# ExpanderBottom.net
KiCad netlist of a schematic drawn in EAGLE
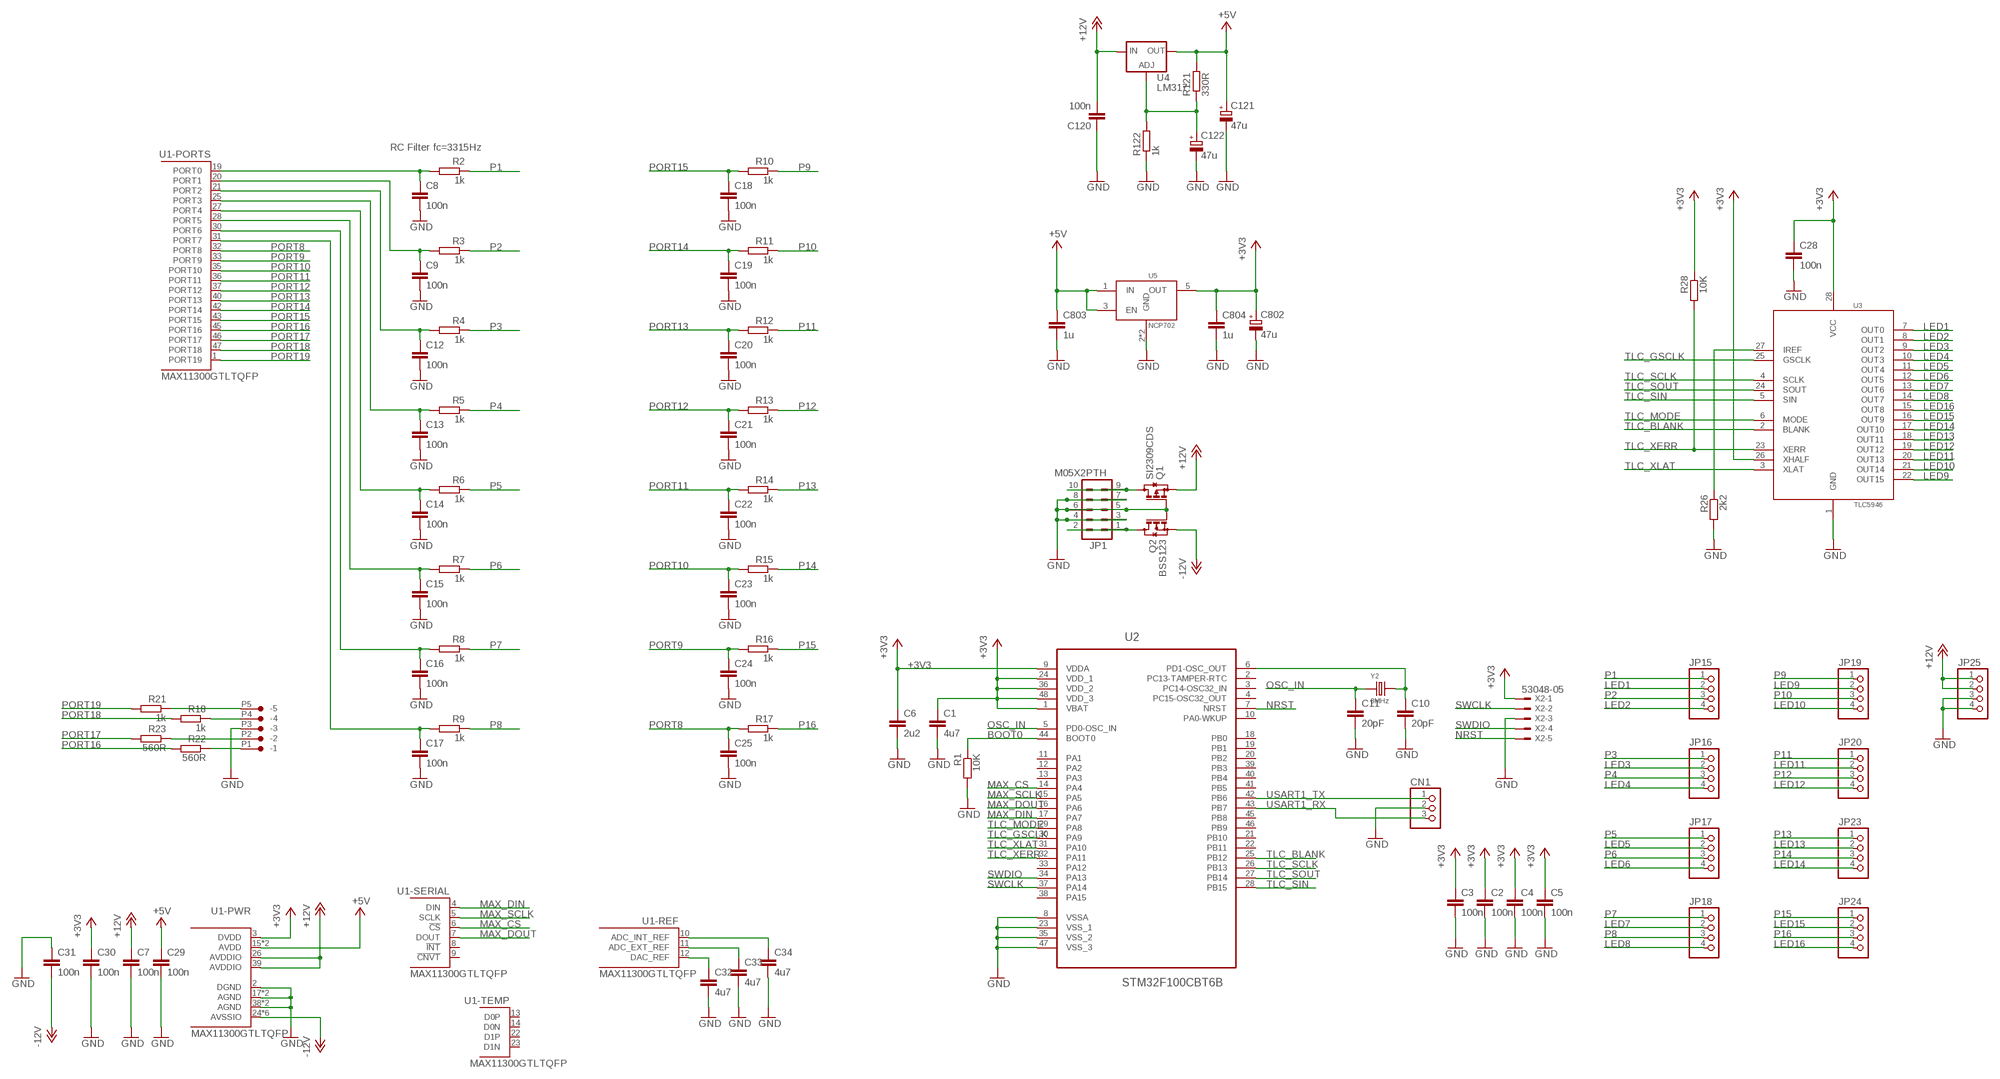
[diagram p0: schematic, sheet 1]

(export (version "E")
  (design (tool "Eeschema 10.0.6"))
  (components
    (comp (ref "5O")
      (value "CON-JST_PH_5W")
      (footprint "eagle-import:CON-JST_PH_5W")
      (libsource (lib "eagle-import") (part "CON-JST_PH_5W"))
    )
    (comp (ref "C1")
      (value "4u7")
      (footprint "eagle-import:C0603")
      (libsource (lib "eagle-import") (part "C-EUC0603"))
    )
    (comp (ref "C2")
      (value "100n")
      (footprint "eagle-import:C0603")
      (libsource (lib "eagle-import") (part "C-EUC0603"))
    )
    (comp (ref "C3")
      (value "100n")
      (footprint "eagle-import:C0603")
      (libsource (lib "eagle-import") (part "C-EUC0603"))
    )
    (comp (ref "C4")
      (value "100n")
      (footprint "eagle-import:C0603")
      (libsource (lib "eagle-import") (part "C-EUC0603"))
    )
    (comp (ref "C5")
      (value "100n")
      (footprint "eagle-import:C0603")
      (libsource (lib "eagle-import") (part "C-EUC0603"))
    )
    (comp (ref "C6")
      (value "2u2")
      (footprint "eagle-import:C0603")
      (libsource (lib "eagle-import") (part "C-EUC0603"))
    )
    (comp (ref "C7")
      (value "100n")
      (footprint "eagle-import:C0603")
      (libsource (lib "eagle-import") (part "C-EUC0603"))
    )
    (comp (ref "C8")
      (value "100n")
      (footprint "eagle-import:C0603")
      (libsource (lib "eagle-import") (part "C-EUC0603"))
    )
    (comp (ref "C9")
      (value "100n")
      (footprint "eagle-import:C0603")
      (libsource (lib "eagle-import") (part "C-EUC0603"))
    )
    (comp (ref "C10")
      (value "20pF")
      (footprint "eagle-import:C0603")
      (libsource (lib "eagle-import") (part "C-EUC0603"))
    )
    (comp (ref "C11")
      (value "20pF")
      (footprint "eagle-import:C0603")
      (libsource (lib "eagle-import") (part "C-EUC0603"))
    )
    (comp (ref "C12")
      (value "100n")
      (footprint "eagle-import:C0603")
      (libsource (lib "eagle-import") (part "C-EUC0603"))
    )
    (comp (ref "C13")
      (value "100n")
      (footprint "eagle-import:C0603")
      (libsource (lib "eagle-import") (part "C-EUC0603"))
    )
    (comp (ref "C14")
      (value "100n")
      (footprint "eagle-import:C0603")
      (libsource (lib "eagle-import") (part "C-EUC0603"))
    )
    (comp (ref "C15")
      (value "100n")
      (footprint "eagle-import:C0603")
      (libsource (lib "eagle-import") (part "C-EUC0603"))
    )
    (comp (ref "C16")
      (value "100n")
      (footprint "eagle-import:C0603")
      (libsource (lib "eagle-import") (part "C-EUC0603"))
    )
    (comp (ref "C17")
      (value "100n")
      (footprint "eagle-import:C0603")
      (libsource (lib "eagle-import") (part "C-EUC0603"))
    )
    (comp (ref "C18")
      (value "100n")
      (footprint "eagle-import:C0603")
      (libsource (lib "eagle-import") (part "C-EUC0603"))
    )
    (comp (ref "C19")
      (value "100n")
      (footprint "eagle-import:C0603")
      (libsource (lib "eagle-import") (part "C-EUC0603"))
    )
    (comp (ref "C20")
      (value "100n")
      (footprint "eagle-import:C0603")
      (libsource (lib "eagle-import") (part "C-EUC0603"))
    )
    (comp (ref "C21")
      (value "100n")
      (footprint "eagle-import:C0603")
      (libsource (lib "eagle-import") (part "C-EUC0603"))
    )
    (comp (ref "C22")
      (value "100n")
      (footprint "eagle-import:C0603")
      (libsource (lib "eagle-import") (part "C-EUC0603"))
    )
    (comp (ref "C23")
      (value "100n")
      (footprint "eagle-import:C0603")
      (libsource (lib "eagle-import") (part "C-EUC0603"))
    )
    (comp (ref "C24")
      (value "100n")
      (footprint "eagle-import:C0603")
      (libsource (lib "eagle-import") (part "C-EUC0603"))
    )
    (comp (ref "C25")
      (value "100n")
      (footprint "eagle-import:C0603")
      (libsource (lib "eagle-import") (part "C-EUC0603"))
    )
    (comp (ref "C28")
      (value "100n")
      (footprint "eagle-import:C0603")
      (libsource (lib "eagle-import") (part "C-EUC0603"))
    )
    (comp (ref "C29")
      (value "100n")
      (footprint "eagle-import:C0603")
      (libsource (lib "eagle-import") (part "C-EUC0603"))
    )
    (comp (ref "C30")
      (value "100n")
      (footprint "eagle-import:C0603")
      (libsource (lib "eagle-import") (part "C-EUC0603"))
    )
    (comp (ref "C31")
      (value "100n")
      (footprint "eagle-import:C0603")
      (libsource (lib "eagle-import") (part "C-EUC0603"))
    )
    (comp (ref "C32")
      (value "4u7")
      (footprint "eagle-import:C0603")
      (libsource (lib "eagle-import") (part "C-EUC0603"))
    )
    (comp (ref "C33")
      (value "4u7")
      (footprint "eagle-import:C0603")
      (libsource (lib "eagle-import") (part "C-EUC0603"))
    )
    (comp (ref "C34")
      (value "4u7")
      (footprint "eagle-import:C0603")
      (libsource (lib "eagle-import") (part "C-EUC0603"))
    )
    (comp (ref "C120")
      (value "100n")
      (footprint "eagle-import:C0603")
      (libsource (lib "eagle-import") (part "C-EUC0603"))
    )
    (comp (ref "C121")
      (value "47u")
      (footprint "eagle-import:CPOL-5")
      (libsource (lib "eagle-import") (part "CPOL-EU153CLV-0505"))
    )
    (comp (ref "C122")
      (value "47u")
      (footprint "eagle-import:CPOL-5")
      (libsource (lib "eagle-import") (part "CPOL-EU153CLV-0505"))
    )
    (comp (ref "C802")
      (value "47u")
      (footprint "eagle-import:CPOL-5")
      (libsource (lib "eagle-import") (part "CPOL-EU153CLV-0505"))
    )
    (comp (ref "C803")
      (value "1u")
      (footprint "eagle-import:C0603")
      (libsource (lib "eagle-import") (part "C-EUC0603"))
    )
    (comp (ref "C804")
      (value "1u")
      (footprint "eagle-import:C0603")
      (libsource (lib "eagle-import") (part "C-EUC0603"))
    )
    (comp (ref "CN1")
      (value "CON-JST-1X03PH-TH")
      (footprint "eagle-import:JST-B3B-PH-KL")
      (libsource (lib "eagle-import") (part "CON-JST-1X03PH-TH"))
    )
    (comp (ref "JP1")
      (value "M05X2PTH")
      (footprint "eagle-import:AVR_ICSP")
      (libsource (lib "eagle-import") (part "M05X2PTH"))
    )
    (comp (ref "JP15")
      (value "PINHD-1X4")
      (footprint "eagle-import:1X04")
      (libsource (lib "eagle-import") (part "PINHD-1X4"))
    )
    (comp (ref "JP16")
      (value "PINHD-1X4")
      (footprint "eagle-import:1X04")
      (libsource (lib "eagle-import") (part "PINHD-1X4"))
    )
    (comp (ref "JP17")
      (value "PINHD-1X4")
      (footprint "eagle-import:1X04")
      (libsource (lib "eagle-import") (part "PINHD-1X4"))
    )
    (comp (ref "JP18")
      (value "PINHD-1X4")
      (footprint "eagle-import:1X04")
      (libsource (lib "eagle-import") (part "PINHD-1X4"))
    )
    (comp (ref "JP19")
      (value "PINHD-1X4")
      (footprint "eagle-import:1X04")
      (libsource (lib "eagle-import") (part "PINHD-1X4"))
    )
    (comp (ref "JP20")
      (value "PINHD-1X4")
      (footprint "eagle-import:1X04")
      (libsource (lib "eagle-import") (part "PINHD-1X4"))
    )
    (comp (ref "JP23")
      (value "PINHD-1X4")
      (footprint "eagle-import:1X04")
      (libsource (lib "eagle-import") (part "PINHD-1X4"))
    )
    (comp (ref "JP24")
      (value "PINHD-1X4")
      (footprint "eagle-import:1X04")
      (libsource (lib "eagle-import") (part "PINHD-1X4"))
    )
    (comp (ref "JP25")
      (value "PINHD-1X4")
      (footprint "eagle-import:1X04")
      (libsource (lib "eagle-import") (part "PINHD-1X4"))
    )
    (comp (ref "Q1")
      (value "SI2309CDS")
      (footprint "eagle-import:SOT23")
      (libsource (lib "eagle-import") (part "BSS84"))
    )
    (comp (ref "Q2")
      (value "BSS123")
      (footprint "eagle-import:SOT23")
      (libsource (lib "eagle-import") (part "BSS123"))
    )
    (comp (ref "R1")
      (value "10K")
      (footprint "eagle-import:0603")
      (libsource (lib "eagle-import") (part "R-EU_0603"))
    )
    (comp (ref "R2")
      (value "1k")
      (footprint "eagle-import:0603")
      (libsource (lib "eagle-import") (part "R-EU_0603"))
    )
    (comp (ref "R3")
      (value "1k")
      (footprint "eagle-import:0603")
      (libsource (lib "eagle-import") (part "R-EU_0603"))
    )
    (comp (ref "R4")
      (value "1k")
      (footprint "eagle-import:0603")
      (libsource (lib "eagle-import") (part "R-EU_0603"))
    )
    (comp (ref "R5")
      (value "1k")
      (footprint "eagle-import:0603")
      (libsource (lib "eagle-import") (part "R-EU_0603"))
    )
    (comp (ref "R6")
      (value "1k")
      (footprint "eagle-import:0603")
      (libsource (lib "eagle-import") (part "R-EU_0603"))
    )
    (comp (ref "R7")
      (value "1k")
      (footprint "eagle-import:0603")
      (libsource (lib "eagle-import") (part "R-EU_0603"))
    )
    (comp (ref "R8")
      (value "1k")
      (footprint "eagle-import:0603")
      (libsource (lib "eagle-import") (part "R-EU_0603"))
    )
    (comp (ref "R9")
      (value "1k")
      (footprint "eagle-import:0603")
      (libsource (lib "eagle-import") (part "R-EU_0603"))
    )
    (comp (ref "R10")
      (value "1k")
      (footprint "eagle-import:0603")
      (libsource (lib "eagle-import") (part "R-EU_0603"))
    )
    (comp (ref "R11")
      (value "1k")
      (footprint "eagle-import:0603")
      (libsource (lib "eagle-import") (part "R-EU_0603"))
    )
    (comp (ref "R12")
      (value "1k")
      (footprint "eagle-import:0603")
      (libsource (lib "eagle-import") (part "R-EU_0603"))
    )
    (comp (ref "R13")
      (value "1k")
      (footprint "eagle-import:0603")
      (libsource (lib "eagle-import") (part "R-EU_0603"))
    )
    (comp (ref "R14")
      (value "1k")
      (footprint "eagle-import:0603")
      (libsource (lib "eagle-import") (part "R-EU_0603"))
    )
    (comp (ref "R15")
      (value "1k")
      (footprint "eagle-import:0603")
      (libsource (lib "eagle-import") (part "R-EU_0603"))
    )
    (comp (ref "R16")
      (value "1k")
      (footprint "eagle-import:0603")
      (libsource (lib "eagle-import") (part "R-EU_0603"))
    )
    (comp (ref "R17")
      (value "1k")
      (footprint "eagle-import:0603")
      (libsource (lib "eagle-import") (part "R-EU_0603"))
    )
    (comp (ref "R18")
      (value "1k")
      (footprint "eagle-import:0603")
      (libsource (lib "eagle-import") (part "R-EU_0603"))
    )
    (comp (ref "R21")
      (value "1k")
      (footprint "eagle-import:0603")
      (libsource (lib "eagle-import") (part "R-EU_0603"))
    )
    (comp (ref "R22")
      (value "560R")
      (footprint "eagle-import:0603")
      (libsource (lib "eagle-import") (part "R-EU_0603"))
    )
    (comp (ref "R23")
      (value "560R")
      (footprint "eagle-import:0603")
      (libsource (lib "eagle-import") (part "R-EU_0603"))
    )
    (comp (ref "R26")
      (value "2k2")
      (footprint "eagle-import:0603")
      (libsource (lib "eagle-import") (part "R-EU_0603"))
    )
    (comp (ref "R28")
      (value "10K")
      (footprint "eagle-import:0603")
      (libsource (lib "eagle-import") (part "R-EU_0603"))
    )
    (comp (ref "R121")
      (value "330R")
      (footprint "eagle-import:0603")
      (libsource (lib "eagle-import") (part "R-EU_0603"))
    )
    (comp (ref "R122")
      (value "1k")
      (footprint "eagle-import:0603")
      (libsource (lib "eagle-import") (part "R-EU_0603"))
    )
    (comp (ref "U1")
      (value "MAX11300GTLTQFP")
      (footprint "eagle-import:TQFP48")
      (libsource (lib "eagle-import") (part "MAX11300GTLTQFP"))
    )
    (comp (ref "U2")
      (value "STM32F100CBT6B")
      (footprint "eagle-import:QFP50P900X900X160-48N")
      (libsource (lib "eagle-import") (part "STM32F100CBT6B"))
    )
    (comp (ref "U3")
      (value "TLC5946")
      (footprint "eagle-import:TSSOP28")
      (libsource (lib "eagle-import") (part "TLC5946"))
    )
    (comp (ref "U4")
      (value "LM317")
      (footprint "eagle-import:SOT223")
      (libsource (lib "eagle-import") (part "LM317?MSTT3"))
    )
    (comp (ref "U5")
      (value "NCP702")
      (footprint "eagle-import:TSOP-5")
      (libsource (lib "eagle-import") (part "NCP702"))
    )
    (comp (ref "X2")
      (value "53048-05")
      (footprint "eagle-import:53048-05")
      (fields (field (name "MF") "MOLEX") (field (name "MPN") "53048-0510"))
      (libsource (lib "eagle-import") (part "53?-05048"))
    )
    (comp (ref "Y2")
      (value "8MHz")
      (footprint "eagle-import:X2-SMD-5.0X3.2X1.3MM")
      (fields (field (name "MPN") "5032/2P"))
      (libsource (lib "eagle-import") (part "SMD-CRYSTAL-8MHZ-20PF-20PPM(2P-5.0X3.2MM)"))
    )
  )
  (nets
    (net (code "1") (name "+3V3") (class "Default")
      (node (ref "C1") (pin "1") (pinfunction "1_1") (pintype "passive"))
      (node (ref "C2") (pin "1") (pinfunction "1_1") (pintype "passive"))
      (node (ref "C28") (pin "1") (pinfunction "1_1") (pintype "passive"))
      (node (ref "C3") (pin "1") (pinfunction "1_1") (pintype "passive"))
      (node (ref "C30") (pin "1") (pinfunction "1_1") (pintype "passive"))
      (node (ref "C4") (pin "1") (pinfunction "1_1") (pintype "passive"))
      (node (ref "C5") (pin "1") (pinfunction "1_1") (pintype "passive"))
      (node (ref "C6") (pin "1") (pinfunction "1_1") (pintype "passive"))
      (node (ref "C802") (pin "+") (pinfunction "+_+") (pintype "passive"))
      (node (ref "C804") (pin "1") (pinfunction "1_1") (pintype "passive"))
      (node (ref "R28") (pin "1") (pinfunction "1_1") (pintype "passive"))
      (node (ref "U1") (pin "3") (pinfunction "DVDD_3") (pintype "bidirectional"))
      (node (ref "U2") (pin "1") (pinfunction "VBAT_1") (pintype "power_in"))
      (node (ref "U2") (pin "24") (pinfunction "VDD_1_24") (pintype "power_in"))
      (node (ref "U2") (pin "36") (pinfunction "VDD_2_36") (pintype "power_in"))
      (node (ref "U2") (pin "48") (pinfunction "VDD_3_48") (pintype "power_in"))
      (node (ref "U2") (pin "9") (pinfunction "VDDA_9") (pintype "power_in"))
      (node (ref "U3") (pin "26") (pinfunction "XHALF_26") (pintype "bidirectional"))
      (node (ref "U3") (pin "28") (pinfunction "VCC_28") (pintype "bidirectional"))
      (node (ref "U5") (pin "5") (pinfunction "OUT_5") (pintype "bidirectional"))
      (node (ref "X2") (pin "1") (pinfunction "S_1") (pintype "passive"))
    )
    (net (code "2") (name "+5V") (class "Default")
      (node (ref "C121") (pin "+") (pinfunction "+_+") (pintype "passive"))
      (node (ref "C29") (pin "1") (pinfunction "1_1") (pintype "passive"))
      (node (ref "C803") (pin "1") (pinfunction "1_1") (pintype "passive"))
      (node (ref "R121") (pin "2") (pinfunction "2_2") (pintype "passive"))
      (node (ref "U1") (pin "15") (pinfunction "AVDD_15") (pintype "bidirectional"))
      (node (ref "U1") (pin "16") (pinfunction "AVDD_16") (pintype "bidirectional"))
      (node (ref "U4") (pin "2") (pinfunction "OUT_2") (pintype "passive"))
      (node (ref "U4") (pin "4") (pinfunction "OUT_4") (pintype "passive"))
      (node (ref "U5") (pin "1") (pinfunction "IN_1") (pintype "bidirectional"))
      (node (ref "U5") (pin "3") (pinfunction "EN_3") (pintype "bidirectional"))
    )
    (net (code "3") (name "+12V") (class "Default")
      (node (ref "C120") (pin "2") (pinfunction "2_2") (pintype "passive"))
      (node (ref "C7") (pin "1") (pinfunction "1_1") (pintype "passive"))
      (node (ref "JP25") (pin "1") (pinfunction "1_1") (pintype "passive"))
      (node (ref "JP25") (pin "2") (pinfunction "2_2") (pintype "passive"))
      (node (ref "Q1") (pin "2") (pinfunction "S_2") (pintype "passive"))
      (node (ref "U1") (pin "26") (pinfunction "AVDDIO_26") (pintype "bidirectional"))
      (node (ref "U1") (pin "39") (pinfunction "AVDDIO_39") (pintype "bidirectional"))
      (node (ref "U4") (pin "3") (pinfunction "IN_3") (pintype "input"))
    )
    (net (code "4") (name "-12V") (class "Default")
      (node (ref "C31") (pin "2") (pinfunction "2_2") (pintype "passive"))
      (node (ref "Q2") (pin "2") (pinfunction "S_2") (pintype "passive"))
      (node (ref "U1") (pin "24") (pinfunction "AVSSIO_24") (pintype "bidirectional"))
      (node (ref "U1") (pin "29") (pinfunction "AVSSIO_29") (pintype "bidirectional"))
      (node (ref "U1") (pin "34") (pinfunction "AVSSIO_34") (pintype "bidirectional"))
      (node (ref "U1") (pin "41") (pinfunction "AVSSIO_41") (pintype "bidirectional"))
      (node (ref "U1") (pin "44") (pinfunction "AVSSIO_44") (pintype "bidirectional"))
      (node (ref "U1") (pin "48") (pinfunction "AVSSIO_48") (pintype "bidirectional"))
    )
    (net (code "5") (name "/BOOT0") (class "Default")
      (node (ref "R1") (pin "1") (pinfunction "1_1") (pintype "passive"))
      (node (ref "U2") (pin "44") (pinfunction "BOOT0_44") (pintype "input"))
    )
    (net (code "6") (name "/LED1") (class "Default")
      (node (ref "JP15") (pin "2") (pinfunction "2_2") (pintype "passive"))
      (node (ref "U3") (pin "7") (pinfunction "OUT0_7") (pintype "bidirectional"))
    )
    (net (code "7") (name "/LED2") (class "Default")
      (node (ref "JP15") (pin "4") (pinfunction "4_4") (pintype "passive"))
      (node (ref "U3") (pin "8") (pinfunction "OUT1_8") (pintype "bidirectional"))
    )
    (net (code "8") (name "/LED3") (class "Default")
      (node (ref "JP16") (pin "2") (pinfunction "2_2") (pintype "passive"))
      (node (ref "U3") (pin "9") (pinfunction "OUT2_9") (pintype "bidirectional"))
    )
    (net (code "9") (name "/LED4") (class "Default")
      (node (ref "JP16") (pin "4") (pinfunction "4_4") (pintype "passive"))
      (node (ref "U3") (pin "10") (pinfunction "OUT3_10") (pintype "bidirectional"))
    )
    (net (code "10") (name "/LED5") (class "Default")
      (node (ref "JP17") (pin "2") (pinfunction "2_2") (pintype "passive"))
      (node (ref "U3") (pin "11") (pinfunction "OUT4_11") (pintype "bidirectional"))
    )
    (net (code "11") (name "/LED6") (class "Default")
      (node (ref "JP17") (pin "4") (pinfunction "4_4") (pintype "passive"))
      (node (ref "U3") (pin "12") (pinfunction "OUT5_12") (pintype "bidirectional"))
    )
    (net (code "12") (name "/LED7") (class "Default")
      (node (ref "JP18") (pin "2") (pinfunction "2_2") (pintype "passive"))
      (node (ref "U3") (pin "13") (pinfunction "OUT6_13") (pintype "bidirectional"))
    )
    (net (code "13") (name "/LED8") (class "Default")
      (node (ref "JP18") (pin "4") (pinfunction "4_4") (pintype "passive"))
      (node (ref "U3") (pin "14") (pinfunction "OUT7_14") (pintype "bidirectional"))
    )
    (net (code "14") (name "/LED9") (class "Default")
      (node (ref "JP19") (pin "2") (pinfunction "2_2") (pintype "passive"))
      (node (ref "U3") (pin "22") (pinfunction "OUT15_22") (pintype "bidirectional"))
    )
    (net (code "15") (name "/LED10") (class "Default")
      (node (ref "JP19") (pin "4") (pinfunction "4_4") (pintype "passive"))
      (node (ref "U3") (pin "21") (pinfunction "OUT14_21") (pintype "bidirectional"))
    )
    (net (code "16") (name "/LED11") (class "Default")
      (node (ref "JP20") (pin "2") (pinfunction "2_2") (pintype "passive"))
      (node (ref "U3") (pin "20") (pinfunction "OUT13_20") (pintype "bidirectional"))
    )
    (net (code "17") (name "/LED12") (class "Default")
      (node (ref "JP20") (pin "4") (pinfunction "4_4") (pintype "passive"))
      (node (ref "U3") (pin "19") (pinfunction "OUT12_19") (pintype "bidirectional"))
    )
    (net (code "18") (name "/LED13") (class "Default")
      (node (ref "JP23") (pin "2") (pinfunction "2_2") (pintype "passive"))
      (node (ref "U3") (pin "18") (pinfunction "OUT11_18") (pintype "bidirectional"))
    )
    (net (code "19") (name "/LED14") (class "Default")
      (node (ref "JP23") (pin "4") (pinfunction "4_4") (pintype "passive"))
      (node (ref "U3") (pin "17") (pinfunction "OUT10_17") (pintype "bidirectional"))
    )
    (net (code "20") (name "/LED15") (class "Default")
      (node (ref "JP24") (pin "2") (pinfunction "2_2") (pintype "passive"))
      (node (ref "U3") (pin "16") (pinfunction "OUT9_16") (pintype "bidirectional"))
    )
    (net (code "21") (name "/LED16") (class "Default")
      (node (ref "JP24") (pin "4") (pinfunction "4_4") (pintype "passive"))
      (node (ref "U3") (pin "15") (pinfunction "OUT8_15") (pintype "bidirectional"))
    )
    (net (code "22") (name "/MAX_CS") (class "Default")
      (node (ref "U1") (pin "6") (pinfunction "~{CS}_6") (pintype "bidirectional"))
      (node (ref "U2") (pin "14") (pinfunction "PA4_14") (pintype "bidirectional"))
    )
    (net (code "23") (name "/MAX_DIN") (class "Default")
      (node (ref "U1") (pin "4") (pinfunction "DIN_4") (pintype "bidirectional"))
      (node (ref "U2") (pin "17") (pinfunction "PA7_17") (pintype "bidirectional"))
    )
    (net (code "24") (name "/MAX_DOUT") (class "Default")
      (node (ref "U1") (pin "7") (pinfunction "DOUT_7") (pintype "bidirectional"))
      (node (ref "U2") (pin "16") (pinfunction "PA6_16") (pintype "bidirectional"))
    )
    (net (code "25") (name "/MAX_SCLK") (class "Default")
      (node (ref "U1") (pin "5") (pinfunction "SCLK_5") (pintype "bidirectional"))
      (node (ref "U2") (pin "15") (pinfunction "PA5_15") (pintype "bidirectional"))
    )
    (net (code "26") (name "/NRST") (class "Default")
      (node (ref "U2") (pin "7") (pinfunction "NRST_7") (pintype "bidirectional"))
      (node (ref "X2") (pin "5") (pinfunction "S_5") (pintype "passive"))
    )
    (net (code "27") (name "/OSC_IN") (class "Default")
      (node (ref "C11") (pin "1") (pinfunction "1_1") (pintype "passive"))
      (node (ref "U2") (pin "5") (pinfunction "PD0-OSC_IN_5") (pintype "input"))
      (node (ref "Y2") (pin "1") (pinfunction "1_1") (pintype "passive"))
    )
    (net (code "28") (name "/P1") (class "Default")
      (node (ref "JP15") (pin "1") (pinfunction "1_1") (pintype "passive"))
      (node (ref "R2") (pin "1") (pinfunction "1_1") (pintype "passive"))
    )
    (net (code "29") (name "/P2") (class "Default")
      (node (ref "JP15") (pin "3") (pinfunction "3_3") (pintype "passive"))
      (node (ref "R3") (pin "1") (pinfunction "1_1") (pintype "passive"))
    )
    (net (code "30") (name "/P3") (class "Default")
      (node (ref "JP16") (pin "1") (pinfunction "1_1") (pintype "passive"))
      (node (ref "R4") (pin "1") (pinfunction "1_1") (pintype "passive"))
    )
    (net (code "31") (name "/P4") (class "Default")
      (node (ref "JP16") (pin "3") (pinfunction "3_3") (pintype "passive"))
      (node (ref "R5") (pin "1") (pinfunction "1_1") (pintype "passive"))
    )
    (net (code "32") (name "/P5") (class "Default")
      (node (ref "JP17") (pin "1") (pinfunction "1_1") (pintype "passive"))
      (node (ref "R6") (pin "1") (pinfunction "1_1") (pintype "passive"))
    )
    (net (code "33") (name "/P6") (class "Default")
      (node (ref "JP17") (pin "3") (pinfunction "3_3") (pintype "passive"))
      (node (ref "R7") (pin "1") (pinfunction "1_1") (pintype "passive"))
    )
    (net (code "34") (name "/P7") (class "Default")
      (node (ref "JP18") (pin "1") (pinfunction "1_1") (pintype "passive"))
      (node (ref "R8") (pin "1") (pinfunction "1_1") (pintype "passive"))
    )
    (net (code "35") (name "/P8") (class "Default")
      (node (ref "JP18") (pin "3") (pinfunction "3_3") (pintype "passive"))
      (node (ref "R9") (pin "1") (pinfunction "1_1") (pintype "passive"))
    )
    (net (code "36") (name "/P9") (class "Default")
      (node (ref "JP19") (pin "1") (pinfunction "1_1") (pintype "passive"))
      (node (ref "R10") (pin "1") (pinfunction "1_1") (pintype "passive"))
    )
    (net (code "37") (name "/P10") (class "Default")
      (node (ref "JP19") (pin "3") (pinfunction "3_3") (pintype "passive"))
      (node (ref "R11") (pin "1") (pinfunction "1_1") (pintype "passive"))
    )
    (net (code "38") (name "/P11") (class "Default")
      (node (ref "JP20") (pin "1") (pinfunction "1_1") (pintype "passive"))
      (node (ref "R12") (pin "1") (pinfunction "1_1") (pintype "passive"))
    )
    (net (code "39") (name "/P12") (class "Default")
      (node (ref "JP20") (pin "3") (pinfunction "3_3") (pintype "passive"))
      (node (ref "R13") (pin "1") (pinfunction "1_1") (pintype "passive"))
    )
    (net (code "40") (name "/P13") (class "Default")
      (node (ref "JP23") (pin "1") (pinfunction "1_1") (pintype "passive"))
      (node (ref "R14") (pin "1") (pinfunction "1_1") (pintype "passive"))
    )
    (net (code "41") (name "/P14") (class "Default")
      (node (ref "JP23") (pin "3") (pinfunction "3_3") (pintype "passive"))
      (node (ref "R15") (pin "1") (pinfunction "1_1") (pintype "passive"))
    )
    (net (code "42") (name "/P15") (class "Default")
      (node (ref "JP24") (pin "1") (pinfunction "1_1") (pintype "passive"))
      (node (ref "R16") (pin "1") (pinfunction "1_1") (pintype "passive"))
    )
    (net (code "43") (name "/P16") (class "Default")
      (node (ref "JP24") (pin "3") (pinfunction "3_3") (pintype "passive"))
      (node (ref "R17") (pin "1") (pinfunction "1_1") (pintype "passive"))
    )
    (net (code "44") (name "/PORT8") (class "Default")
      (node (ref "C25") (pin "1") (pinfunction "1_1") (pintype "passive"))
      (node (ref "R17") (pin "2") (pinfunction "2_2") (pintype "passive"))
      (node (ref "U1") (pin "32") (pinfunction "PORT8_32") (pintype "bidirectional"))
    )
    (net (code "45") (name "/PORT9") (class "Default")
      (node (ref "C24") (pin "1") (pinfunction "1_1") (pintype "passive"))
      (node (ref "R16") (pin "2") (pinfunction "2_2") (pintype "passive"))
      (node (ref "U1") (pin "33") (pinfunction "PORT9_33") (pintype "bidirectional"))
    )
    (net (code "46") (name "/PORT10") (class "Default")
      (node (ref "C23") (pin "1") (pinfunction "1_1") (pintype "passive"))
      (node (ref "R15") (pin "2") (pinfunction "2_2") (pintype "passive"))
      (node (ref "U1") (pin "35") (pinfunction "PORT10_35") (pintype "bidirectional"))
    )
    (net (code "47") (name "/PORT11") (class "Default")
      (node (ref "C22") (pin "1") (pinfunction "1_1") (pintype "passive"))
      (node (ref "R14") (pin "2") (pinfunction "2_2") (pintype "passive"))
      (node (ref "U1") (pin "36") (pinfunction "PORT11_36") (pintype "bidirectional"))
    )
    (net (code "48") (name "/PORT12") (class "Default")
      (node (ref "C21") (pin "1") (pinfunction "1_1") (pintype "passive"))
      (node (ref "R13") (pin "2") (pinfunction "2_2") (pintype "passive"))
      (node (ref "U1") (pin "37") (pinfunction "PORT12_37") (pintype "bidirectional"))
    )
    (net (code "49") (name "/PORT13") (class "Default")
      (node (ref "C20") (pin "1") (pinfunction "1_1") (pintype "passive"))
      (node (ref "R12") (pin "2") (pinfunction "2_2") (pintype "passive"))
      (node (ref "U1") (pin "40") (pinfunction "PORT13_40") (pintype "bidirectional"))
    )
    (net (code "50") (name "/PORT14") (class "Default")
      (node (ref "C19") (pin "1") (pinfunction "1_1") (pintype "passive"))
      (node (ref "R11") (pin "2") (pinfunction "2_2") (pintype "passive"))
      (node (ref "U1") (pin "42") (pinfunction "PORT14_42") (pintype "bidirectional"))
    )
    (net (code "51") (name "/PORT15") (class "Default")
      (node (ref "C18") (pin "1") (pinfunction "1_1") (pintype "passive"))
      (node (ref "R10") (pin "2") (pinfunction "2_2") (pintype "passive"))
      (node (ref "U1") (pin "43") (pinfunction "PORT15_43") (pintype "bidirectional"))
    )
    (net (code "52") (name "/PORT16") (class "Default")
      (node (ref "R22") (pin "2") (pinfunction "2_2") (pintype "passive"))
      (node (ref "U1") (pin "45") (pinfunction "PORT16_45") (pintype "bidirectional"))
    )
    (net (code "53") (name "/PORT17") (class "Default")
      (node (ref "R23") (pin "2") (pinfunction "2_2") (pintype "passive"))
      (node (ref "U1") (pin "46") (pinfunction "PORT17_46") (pintype "bidirectional"))
    )
    (net (code "54") (name "/PORT18") (class "Default")
      (node (ref "R18") (pin "2") (pinfunction "2_2") (pintype "passive"))
      (node (ref "U1") (pin "47") (pinfunction "PORT18_47") (pintype "bidirectional"))
    )
    (net (code "55") (name "/PORT19") (class "Default")
      (node (ref "R21") (pin "2") (pinfunction "2_2") (pintype "passive"))
      (node (ref "U1") (pin "1") (pinfunction "PORT19_1") (pintype "bidirectional"))
    )
    (net (code "56") (name "/SWCLK") (class "Default")
      (node (ref "U2") (pin "37") (pinfunction "PA14_37") (pintype "bidirectional"))
      (node (ref "X2") (pin "2") (pinfunction "S_2") (pintype "passive"))
    )
    (net (code "57") (name "/SWDIO") (class "Default")
      (node (ref "U2") (pin "34") (pinfunction "PA13_34") (pintype "bidirectional"))
      (node (ref "X2") (pin "4") (pinfunction "S_4") (pintype "passive"))
    )
    (net (code "58") (name "/TLC_BLANK") (class "Default")
      (node (ref "U2") (pin "25") (pinfunction "PB12_25") (pintype "bidirectional"))
      (node (ref "U3") (pin "2") (pinfunction "BLANK_2") (pintype "bidirectional"))
    )
    (net (code "59") (name "/TLC_GSCLK") (class "Default")
      (node (ref "U2") (pin "30") (pinfunction "PA9_30") (pintype "bidirectional"))
      (node (ref "U3") (pin "25") (pinfunction "GSCLK_25") (pintype "bidirectional"))
    )
    (net (code "60") (name "/TLC_MODE") (class "Default")
      (node (ref "U2") (pin "29") (pinfunction "PA8_29") (pintype "bidirectional"))
      (node (ref "U3") (pin "6") (pinfunction "MODE_6") (pintype "bidirectional"))
    )
    (net (code "61") (name "/TLC_SCLK") (class "Default")
      (node (ref "U2") (pin "26") (pinfunction "PB13_26") (pintype "bidirectional"))
      (node (ref "U3") (pin "4") (pinfunction "SCLK_4") (pintype "bidirectional"))
    )
    (net (code "62") (name "/TLC_SIN") (class "Default")
      (node (ref "U2") (pin "28") (pinfunction "PB15_28") (pintype "bidirectional"))
      (node (ref "U3") (pin "5") (pinfunction "SIN_5") (pintype "bidirectional"))
    )
    (net (code "63") (name "/TLC_SOUT") (class "Default")
      (node (ref "U2") (pin "27") (pinfunction "PB14_27") (pintype "bidirectional"))
      (node (ref "U3") (pin "24") (pinfunction "SOUT_24") (pintype "bidirectional"))
    )
    (net (code "64") (name "/TLC_XERR") (class "Default")
      (node (ref "R28") (pin "2") (pinfunction "2_2") (pintype "passive"))
      (node (ref "U2") (pin "32") (pinfunction "PA11_32") (pintype "bidirectional"))
      (node (ref "U3") (pin "23") (pinfunction "XERR_23") (pintype "bidirectional"))
    )
    (net (code "65") (name "/TLC_XLAT") (class "Default")
      (node (ref "U2") (pin "31") (pinfunction "PA10_31") (pintype "bidirectional"))
      (node (ref "U3") (pin "3") (pinfunction "XLAT_3") (pintype "bidirectional"))
    )
    (net (code "66") (name "/USART1_RX") (class "Default")
      (node (ref "CN1") (pin "3") (pinfunction "3_3") (pintype "passive"))
      (node (ref "U2") (pin "43") (pinfunction "PB7_43") (pintype "bidirectional"))
    )
    (net (code "67") (name "/USART1_TX") (class "Default")
      (node (ref "CN1") (pin "1") (pinfunction "1_1") (pintype "passive"))
      (node (ref "U2") (pin "42") (pinfunction "PB6_42") (pintype "bidirectional"))
    )
    (net (code "68") (name "GND") (class "Default")
      (node (ref "5O") (pin "P3") (pinfunction "-3_P3") (pintype "bidirectional"))
      (node (ref "C1") (pin "2") (pinfunction "2_2") (pintype "passive"))
      (node (ref "C10") (pin "2") (pinfunction "2_2") (pintype "passive"))
      (node (ref "C11") (pin "2") (pinfunction "2_2") (pintype "passive"))
      (node (ref "C12") (pin "2") (pinfunction "2_2") (pintype "passive"))
      (node (ref "C120") (pin "1") (pinfunction "1_1") (pintype "passive"))
      (node (ref "C121") (pin "-") (pinfunction "-_-") (pintype "passive"))
      (node (ref "C122") (pin "-") (pinfunction "-_-") (pintype "passive"))
      (node (ref "C13") (pin "2") (pinfunction "2_2") (pintype "passive"))
      (node (ref "C14") (pin "2") (pinfunction "2_2") (pintype "passive"))
      (node (ref "C15") (pin "2") (pinfunction "2_2") (pintype "passive"))
      (node (ref "C16") (pin "2") (pinfunction "2_2") (pintype "passive"))
      (node (ref "C17") (pin "2") (pinfunction "2_2") (pintype "passive"))
      (node (ref "C18") (pin "2") (pinfunction "2_2") (pintype "passive"))
      (node (ref "C19") (pin "2") (pinfunction "2_2") (pintype "passive"))
      (node (ref "C2") (pin "2") (pinfunction "2_2") (pintype "passive"))
      (node (ref "C20") (pin "2") (pinfunction "2_2") (pintype "passive"))
      (node (ref "C21") (pin "2") (pinfunction "2_2") (pintype "passive"))
      (node (ref "C22") (pin "2") (pinfunction "2_2") (pintype "passive"))
      (node (ref "C23") (pin "2") (pinfunction "2_2") (pintype "passive"))
      (node (ref "C24") (pin "2") (pinfunction "2_2") (pintype "passive"))
      (node (ref "C25") (pin "2") (pinfunction "2_2") (pintype "passive"))
      (node (ref "C28") (pin "2") (pinfunction "2_2") (pintype "passive"))
      (node (ref "C29") (pin "2") (pinfunction "2_2") (pintype "passive"))
      (node (ref "C3") (pin "2") (pinfunction "2_2") (pintype "passive"))
      (node (ref "C30") (pin "2") (pinfunction "2_2") (pintype "passive"))
      (node (ref "C31") (pin "1") (pinfunction "1_1") (pintype "passive"))
      (node (ref "C32") (pin "2") (pinfunction "2_2") (pintype "passive"))
      (node (ref "C33") (pin "2") (pinfunction "2_2") (pintype "passive"))
      (node (ref "C34") (pin "2") (pinfunction "2_2") (pintype "passive"))
      (node (ref "C4") (pin "2") (pinfunction "2_2") (pintype "passive"))
      (node (ref "C5") (pin "2") (pinfunction "2_2") (pintype "passive"))
      (node (ref "C6") (pin "2") (pinfunction "2_2") (pintype "passive"))
      (node (ref "C7") (pin "2") (pinfunction "2_2") (pintype "passive"))
      (node (ref "C8") (pin "2") (pinfunction "2_2") (pintype "passive"))
      (node (ref "C802") (pin "-") (pinfunction "-_-") (pintype "passive"))
      (node (ref "C803") (pin "2") (pinfunction "2_2") (pintype "passive"))
      (node (ref "C804") (pin "2") (pinfunction "2_2") (pintype "passive"))
      (node (ref "C9") (pin "2") (pinfunction "2_2") (pintype "passive"))
      (node (ref "CN1") (pin "2") (pinfunction "2_2") (pintype "passive"))
      (node (ref "JP1") (pin "3") (pinfunction "3_3") (pintype "passive"))
      (node (ref "JP1") (pin "4") (pinfunction "4_4") (pintype "passive"))
      (node (ref "JP1") (pin "5") (pinfunction "5_5") (pintype "passive"))
      (node (ref "JP1") (pin "6") (pinfunction "6_6") (pintype "passive"))
      (node (ref "JP1") (pin "7") (pinfunction "7_7") (pintype "passive"))
      (node (ref "JP1") (pin "8") (pinfunction "8_8") (pintype "passive"))
      (node (ref "JP25") (pin "3") (pinfunction "3_3") (pintype "passive"))
      (node (ref "JP25") (pin "4") (pinfunction "4_4") (pintype "passive"))
      (node (ref "Q1") (pin "1") (pinfunction "G_1") (pintype "passive"))
      (node (ref "Q2") (pin "1") (pinfunction "G_1") (pintype "passive"))
      (node (ref "R1") (pin "2") (pinfunction "2_2") (pintype "passive"))
      (node (ref "R122") (pin "1") (pinfunction "1_1") (pintype "passive"))
      (node (ref "R26") (pin "2") (pinfunction "2_2") (pintype "passive"))
      (node (ref "U1") (pin "17") (pinfunction "AGND_17") (pintype "bidirectional"))
      (node (ref "U1") (pin "18") (pinfunction "AGND_18") (pintype "bidirectional"))
      (node (ref "U1") (pin "2") (pinfunction "DGND_2") (pintype "bidirectional"))
      (node (ref "U1") (pin "38") (pinfunction "AGND_38") (pintype "bidirectional"))
      (node (ref "U1") (pin "EP") (pinfunction "AGND_EP") (pintype "bidirectional"))
      (node (ref "U2") (pin "23") (pinfunction "VSS_1_23") (pintype "power_in"))
      (node (ref "U2") (pin "35") (pinfunction "VSS_2_35") (pintype "power_in"))
      (node (ref "U2") (pin "47") (pinfunction "VSS_3_47") (pintype "power_in"))
      (node (ref "U2") (pin "8") (pinfunction "VSSA_8") (pintype "power_in"))
      (node (ref "U3") (pin "1") (pinfunction "GND_1") (pintype "bidirectional"))
      (node (ref "U5") (pin "2") (pinfunction "GND_2") (pintype "bidirectional"))
      (node (ref "U5") (pin "4") (pinfunction "GND_4") (pintype "bidirectional"))
      (node (ref "X2") (pin "3") (pinfunction "S_3") (pintype "passive"))
    )
    (net (code "69") (name "Net-(5O--1)") (class "Default")
      (node (ref "5O") (pin "P1") (pinfunction "-1_P1") (pintype "bidirectional"))
      (node (ref "R22") (pin "1") (pinfunction "1_1") (pintype "passive"))
    )
    (net (code "70") (name "Net-(5O--2)") (class "Default")
      (node (ref "5O") (pin "P2") (pinfunction "-2_P2") (pintype "bidirectional"))
      (node (ref "R23") (pin "1") (pinfunction "1_1") (pintype "passive"))
    )
    (net (code "71") (name "Net-(5O--4)") (class "Default")
      (node (ref "5O") (pin "P4") (pinfunction "-4_P4") (pintype "bidirectional"))
      (node (ref "R18") (pin "1") (pinfunction "1_1") (pintype "passive"))
    )
    (net (code "72") (name "Net-(5O--5)") (class "Default")
      (node (ref "5O") (pin "P5") (pinfunction "-5_P5") (pintype "bidirectional"))
      (node (ref "R21") (pin "1") (pinfunction "1_1") (pintype "passive"))
    )
    (net (code "73") (name "Net-(Q1-D)") (class "Default")
      (node (ref "JP1") (pin "10") (pinfunction "10_10") (pintype "passive"))
      (node (ref "JP1") (pin "9") (pinfunction "9_9") (pintype "passive"))
      (node (ref "Q1") (pin "3") (pinfunction "D_3") (pintype "passive"))
    )
    (net (code "74") (name "Net-(Q2-D)") (class "Default")
      (node (ref "JP1") (pin "1") (pinfunction "1_1") (pintype "passive"))
      (node (ref "JP1") (pin "2") (pinfunction "2_2") (pintype "passive"))
      (node (ref "Q2") (pin "3") (pinfunction "D_3") (pintype "passive"))
    )
    (net (code "75") (name "Net-(U1A-PORT0)") (class "Default")
      (node (ref "C8") (pin "1") (pinfunction "1_1") (pintype "passive"))
      (node (ref "R2") (pin "2") (pinfunction "2_2") (pintype "passive"))
      (node (ref "U1") (pin "19") (pinfunction "PORT0_19") (pintype "bidirectional"))
    )
    (net (code "76") (name "Net-(U1A-PORT1)") (class "Default")
      (node (ref "C9") (pin "1") (pinfunction "1_1") (pintype "passive"))
      (node (ref "R3") (pin "2") (pinfunction "2_2") (pintype "passive"))
      (node (ref "U1") (pin "20") (pinfunction "PORT1_20") (pintype "bidirectional"))
    )
    (net (code "77") (name "Net-(U1A-PORT2)") (class "Default")
      (node (ref "C12") (pin "1") (pinfunction "1_1") (pintype "passive"))
      (node (ref "R4") (pin "2") (pinfunction "2_2") (pintype "passive"))
      (node (ref "U1") (pin "21") (pinfunction "PORT2_21") (pintype "bidirectional"))
    )
    (net (code "78") (name "Net-(U1A-PORT3)") (class "Default")
      (node (ref "C13") (pin "1") (pinfunction "1_1") (pintype "passive"))
      (node (ref "R5") (pin "2") (pinfunction "2_2") (pintype "passive"))
      (node (ref "U1") (pin "25") (pinfunction "PORT3_25") (pintype "bidirectional"))
    )
    (net (code "79") (name "Net-(U1A-PORT4)") (class "Default")
      (node (ref "C14") (pin "1") (pinfunction "1_1") (pintype "passive"))
      (node (ref "R6") (pin "2") (pinfunction "2_2") (pintype "passive"))
      (node (ref "U1") (pin "27") (pinfunction "PORT4_27") (pintype "bidirectional"))
    )
    (net (code "80") (name "Net-(U1A-PORT5)") (class "Default")
      (node (ref "C15") (pin "1") (pinfunction "1_1") (pintype "passive"))
      (node (ref "R7") (pin "2") (pinfunction "2_2") (pintype "passive"))
      (node (ref "U1") (pin "28") (pinfunction "PORT5_28") (pintype "bidirectional"))
    )
    (net (code "81") (name "Net-(U1A-PORT6)") (class "Default")
      (node (ref "C16") (pin "1") (pinfunction "1_1") (pintype "passive"))
      (node (ref "R8") (pin "2") (pinfunction "2_2") (pintype "passive"))
      (node (ref "U1") (pin "30") (pinfunction "PORT6_30") (pintype "bidirectional"))
    )
    (net (code "82") (name "Net-(U1A-PORT7)") (class "Default")
      (node (ref "C17") (pin "1") (pinfunction "1_1") (pintype "passive"))
      (node (ref "R9") (pin "2") (pinfunction "2_2") (pintype "passive"))
      (node (ref "U1") (pin "31") (pinfunction "PORT7_31") (pintype "bidirectional"))
    )
    (net (code "83") (name "Net-(U1C-ADC_EXT_REF)") (class "Default")
      (node (ref "C33") (pin "1") (pinfunction "1_1") (pintype "passive"))
      (node (ref "U1") (pin "11") (pinfunction "ADC_EXT_REF_11") (pintype "bidirectional"))
    )
    (net (code "84") (name "Net-(U1C-ADC_INT_REF)") (class "Default")
      (node (ref "C34") (pin "1") (pinfunction "1_1") (pintype "passive"))
      (node (ref "U1") (pin "10") (pinfunction "ADC_INT_REF_10") (pintype "bidirectional"))
    )
    (net (code "85") (name "Net-(U1C-DAC_REF)") (class "Default")
      (node (ref "C32") (pin "1") (pinfunction "1_1") (pintype "passive"))
      (node (ref "U1") (pin "12") (pinfunction "DAC_REF_12") (pintype "bidirectional"))
    )
    (net (code "86") (name "Net-(U2-PD1-OSC_OUT)") (class "Default")
      (node (ref "C10") (pin "1") (pinfunction "1_1") (pintype "passive"))
      (node (ref "U2") (pin "6") (pinfunction "PD1-OSC_OUT_6") (pintype "output"))
      (node (ref "Y2") (pin "2") (pinfunction "2_2") (pintype "passive"))
    )
    (net (code "87") (name "Net-(U3-IREF)") (class "Default")
      (node (ref "R26") (pin "1") (pinfunction "1_1") (pintype "passive"))
      (node (ref "U3") (pin "27") (pinfunction "IREF_27") (pintype "bidirectional"))
    )
    (net (code "88") (name "Net-(U4-ADJ)") (class "Default")
      (node (ref "C122") (pin "+") (pinfunction "+_+") (pintype "passive"))
      (node (ref "R121") (pin "1") (pinfunction "1_1") (pintype "passive"))
      (node (ref "R122") (pin "2") (pinfunction "2_2") (pintype "passive"))
      (node (ref "U4") (pin "1") (pinfunction "ADJ_1") (pintype "input"))
    )
    (net (code "89") (name "unconnected-(U1D-~{CNVT}-Pad9)") (class "Default")
      (node (ref "U1") (pin "9") (pinfunction "~{CNVT}_9") (pintype "bidirectional"))
    )
    (net (code "90") (name "unconnected-(U1D-~{INT}-Pad8)") (class "Default")
      (node (ref "U1") (pin "8") (pinfunction "~{INT}_8") (pintype "bidirectional"))
    )
    (net (code "91") (name "unconnected-(U1E-D0N-Pad14)") (class "Default")
      (node (ref "U1") (pin "14") (pinfunction "D0N_14") (pintype "bidirectional"))
    )
    (net (code "92") (name "unconnected-(U1E-D0P-Pad13)") (class "Default")
      (node (ref "U1") (pin "13") (pinfunction "D0P_13") (pintype "bidirectional"))
    )
    (net (code "93") (name "unconnected-(U1E-D1N-Pad23)") (class "Default")
      (node (ref "U1") (pin "23") (pinfunction "D1N_23") (pintype "bidirectional"))
    )
    (net (code "94") (name "unconnected-(U1E-D1P-Pad22)") (class "Default")
      (node (ref "U1") (pin "22") (pinfunction "D1P_22") (pintype "bidirectional"))
    )
    (net (code "95") (name "unconnected-(U2-PA0-WKUP-Pad10)") (class "Default")
      (node (ref "U2") (pin "10") (pinfunction "PA0-WKUP_10") (pintype "bidirectional"))
    )
    (net (code "96") (name "unconnected-(U2-PA1-Pad11)") (class "Default")
      (node (ref "U2") (pin "11") (pinfunction "PA1_11") (pintype "bidirectional"))
    )
    (net (code "97") (name "unconnected-(U2-PA2-Pad12)") (class "Default")
      (node (ref "U2") (pin "12") (pinfunction "PA2_12") (pintype "bidirectional"))
    )
    (net (code "98") (name "unconnected-(U2-PA3-Pad13)") (class "Default")
      (node (ref "U2") (pin "13") (pinfunction "PA3_13") (pintype "bidirectional"))
    )
    (net (code "99") (name "unconnected-(U2-PA12-Pad33)") (class "Default")
      (node (ref "U2") (pin "33") (pinfunction "PA12_33") (pintype "bidirectional"))
    )
    (net (code "100") (name "unconnected-(U2-PA15-Pad38)") (class "Default")
      (node (ref "U2") (pin "38") (pinfunction "PA15_38") (pintype "bidirectional"))
    )
    (net (code "101") (name "unconnected-(U2-PB0-Pad18)") (class "Default")
      (node (ref "U2") (pin "18") (pinfunction "PB0_18") (pintype "bidirectional"))
    )
    (net (code "102") (name "unconnected-(U2-PB1-Pad19)") (class "Default")
      (node (ref "U2") (pin "19") (pinfunction "PB1_19") (pintype "bidirectional"))
    )
    (net (code "103") (name "unconnected-(U2-PB2-Pad20)") (class "Default")
      (node (ref "U2") (pin "20") (pinfunction "PB2_20") (pintype "bidirectional"))
    )
    (net (code "104") (name "unconnected-(U2-PB3-Pad39)") (class "Default")
      (node (ref "U2") (pin "39") (pinfunction "PB3_39") (pintype "bidirectional"))
    )
    (net (code "105") (name "unconnected-(U2-PB4-Pad40)") (class "Default")
      (node (ref "U2") (pin "40") (pinfunction "PB4_40") (pintype "bidirectional"))
    )
    (net (code "106") (name "unconnected-(U2-PB5-Pad41)") (class "Default")
      (node (ref "U2") (pin "41") (pinfunction "PB5_41") (pintype "bidirectional"))
    )
    (net (code "107") (name "unconnected-(U2-PB8-Pad45)") (class "Default")
      (node (ref "U2") (pin "45") (pinfunction "PB8_45") (pintype "bidirectional"))
    )
    (net (code "108") (name "unconnected-(U2-PB9-Pad46)") (class "Default")
      (node (ref "U2") (pin "46") (pinfunction "PB9_46") (pintype "bidirectional"))
    )
    (net (code "109") (name "unconnected-(U2-PB10-Pad21)") (class "Default")
      (node (ref "U2") (pin "21") (pinfunction "PB10_21") (pintype "bidirectional"))
    )
    (net (code "110") (name "unconnected-(U2-PB11-Pad22)") (class "Default")
      (node (ref "U2") (pin "22") (pinfunction "PB11_22") (pintype "bidirectional"))
    )
    (net (code "111") (name "unconnected-(U2-PC13-TAMPER-RTC-Pad2)") (class "Default")
      (node (ref "U2") (pin "2") (pinfunction "PC13-TAMPER-RTC_2") (pintype "bidirectional"))
    )
    (net (code "112") (name "unconnected-(U2-PC14-OSC32_IN-Pad3)") (class "Default")
      (node (ref "U2") (pin "3") (pinfunction "PC14-OSC32_IN_3") (pintype "bidirectional"))
    )
    (net (code "113") (name "unconnected-(U2-PC15-OSC32_OUT-Pad4)") (class "Default")
      (node (ref "U2") (pin "4") (pinfunction "PC15-OSC32_OUT_4") (pintype "bidirectional"))
    )
  )
)
